# 00A-001.net
KiCad netlist of a schematic drawn in EAGLE
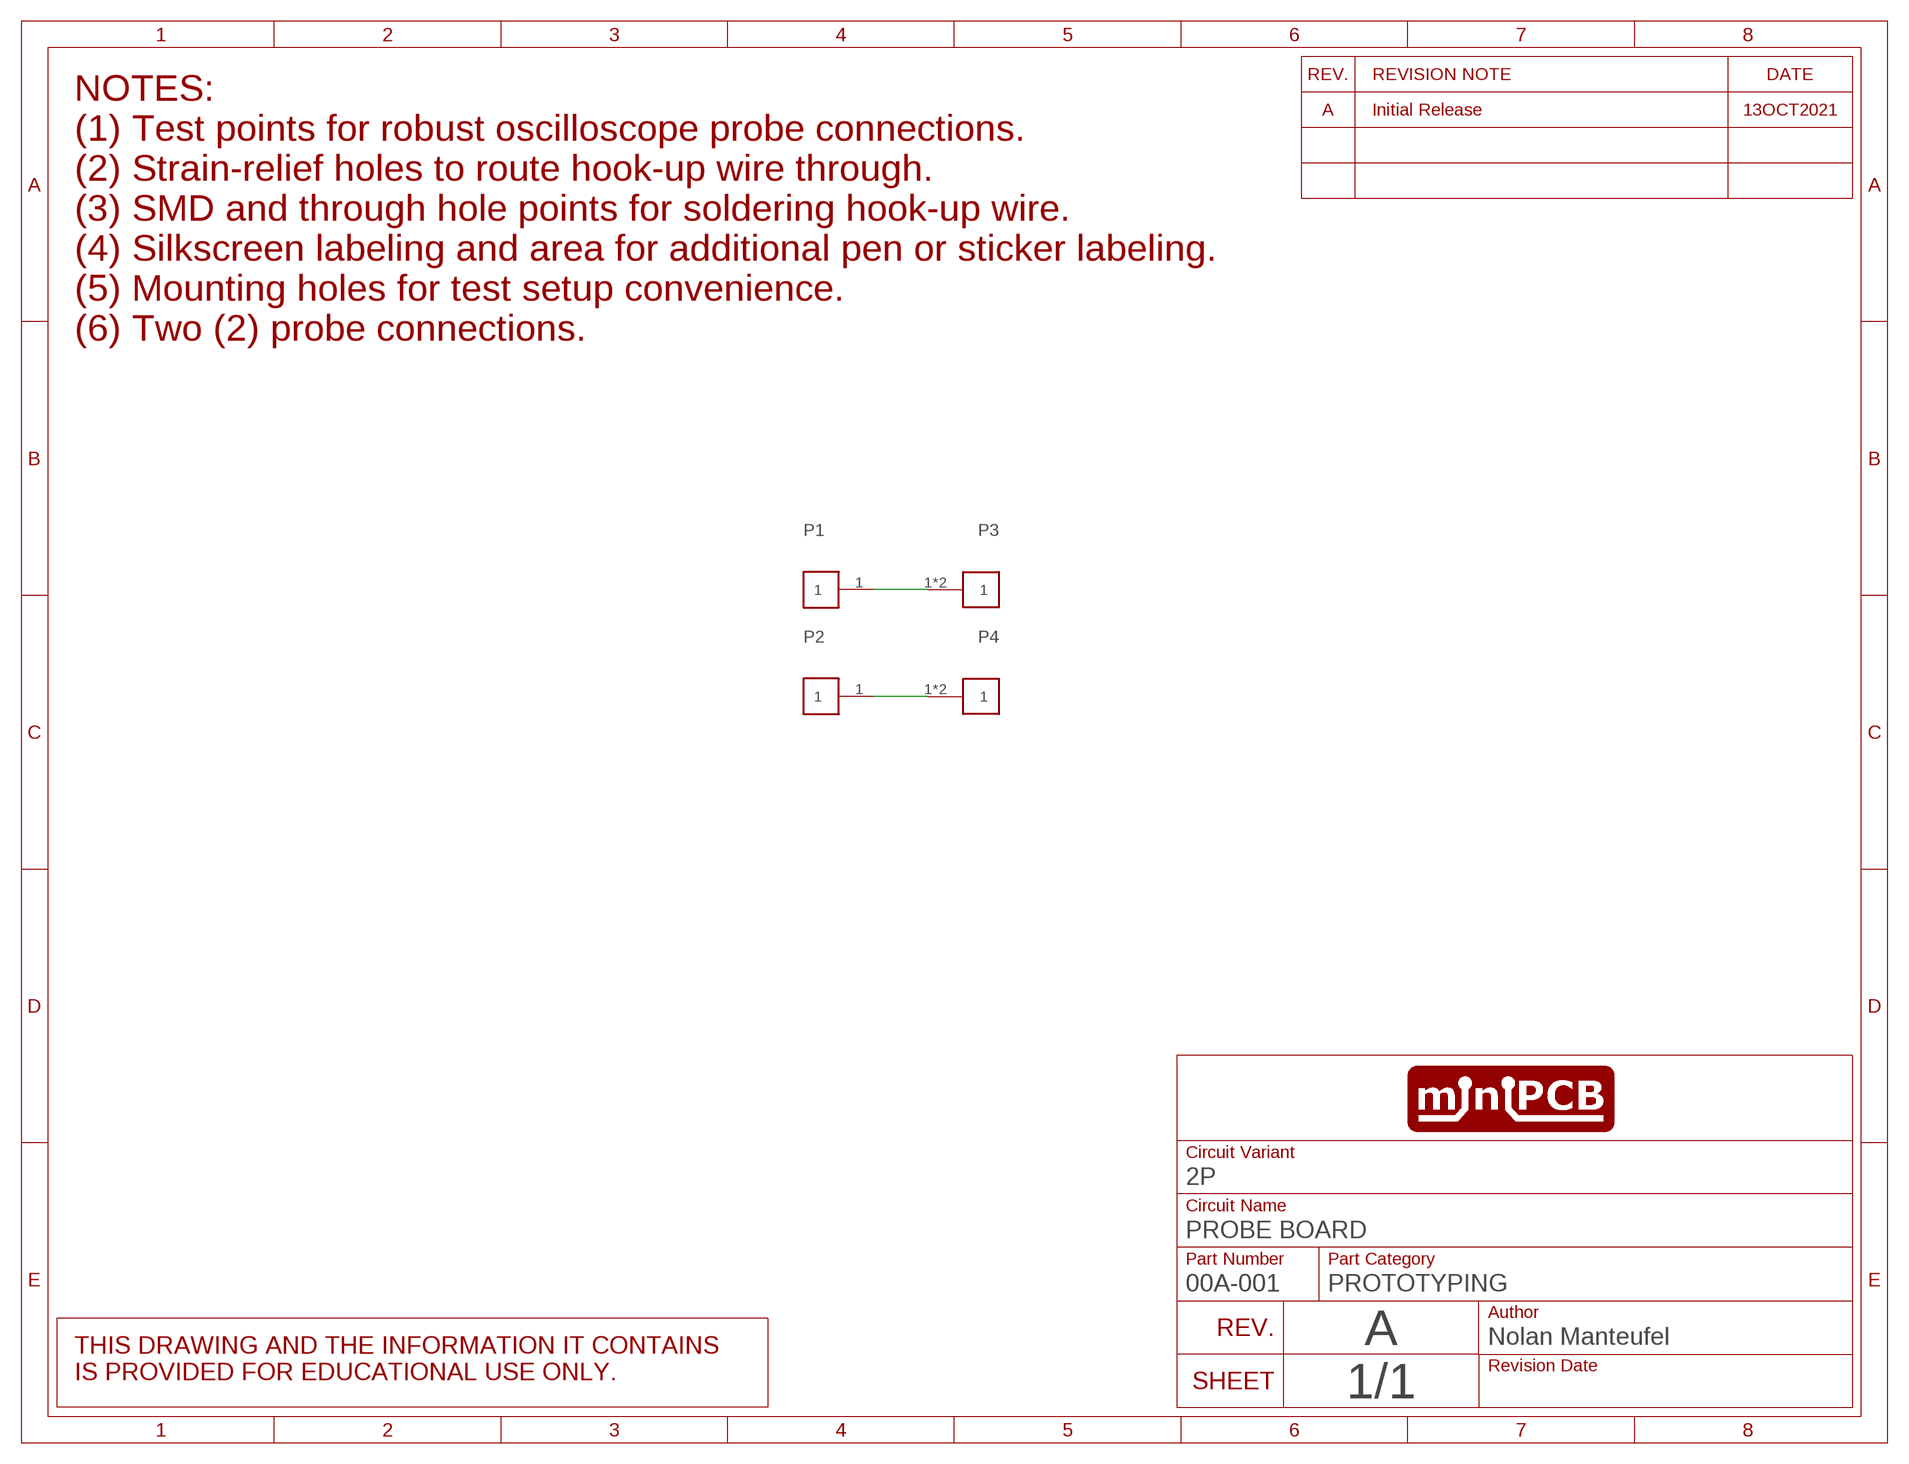
[diagram p0: schematic, sheet 1]

(export (version "E")
  (design (tool "Eeschema 10.0.6"))
  (components
    (comp (ref "P1")
      (value "PINS_1KE_5000")
      (footprint "eagle-import:PINS_1_TESTPOINT_KE5000")
      (libsource (lib "eagle-import") (part "PINS_1KE_5000"))
    )
    (comp (ref "P2")
      (value "PINS_1KE_5000")
      (footprint "eagle-import:PINS_1_TESTPOINT_KE5000")
      (libsource (lib "eagle-import") (part "PINS_1KE_5000"))
    )
    (comp (ref "P3")
      (value "PINS_124AWG")
      (footprint "eagle-import:PINS_1_1MM")
      (libsource (lib "eagle-import") (part "PINS_124AWG"))
    )
    (comp (ref "P4")
      (value "PINS_124AWG")
      (footprint "eagle-import:PINS_1_1MM")
      (libsource (lib "eagle-import") (part "PINS_124AWG"))
    )
  )
  (nets
    (net (code "1") (name "Net-(P1-Pad1)") (class "Default")
      (node (ref "P1") (pin "1") (pinfunction "1_1") (pintype "bidirectional"))
      (node (ref "P3") (pin "1") (pinfunction "1_1") (pintype "bidirectional"))
      (node (ref "P3") (pin "2") (pinfunction "1_2") (pintype "bidirectional"))
    )
    (net (code "2") (name "Net-(P2-Pad1)") (class "Default")
      (node (ref "P2") (pin "1") (pinfunction "1_1") (pintype "bidirectional"))
      (node (ref "P4") (pin "1") (pinfunction "1_1") (pintype "bidirectional"))
      (node (ref "P4") (pin "2") (pinfunction "1_2") (pintype "bidirectional"))
    )
  )
)
